# avrdmxsmt.net
KiCad netlist of a schematic drawn in EAGLE
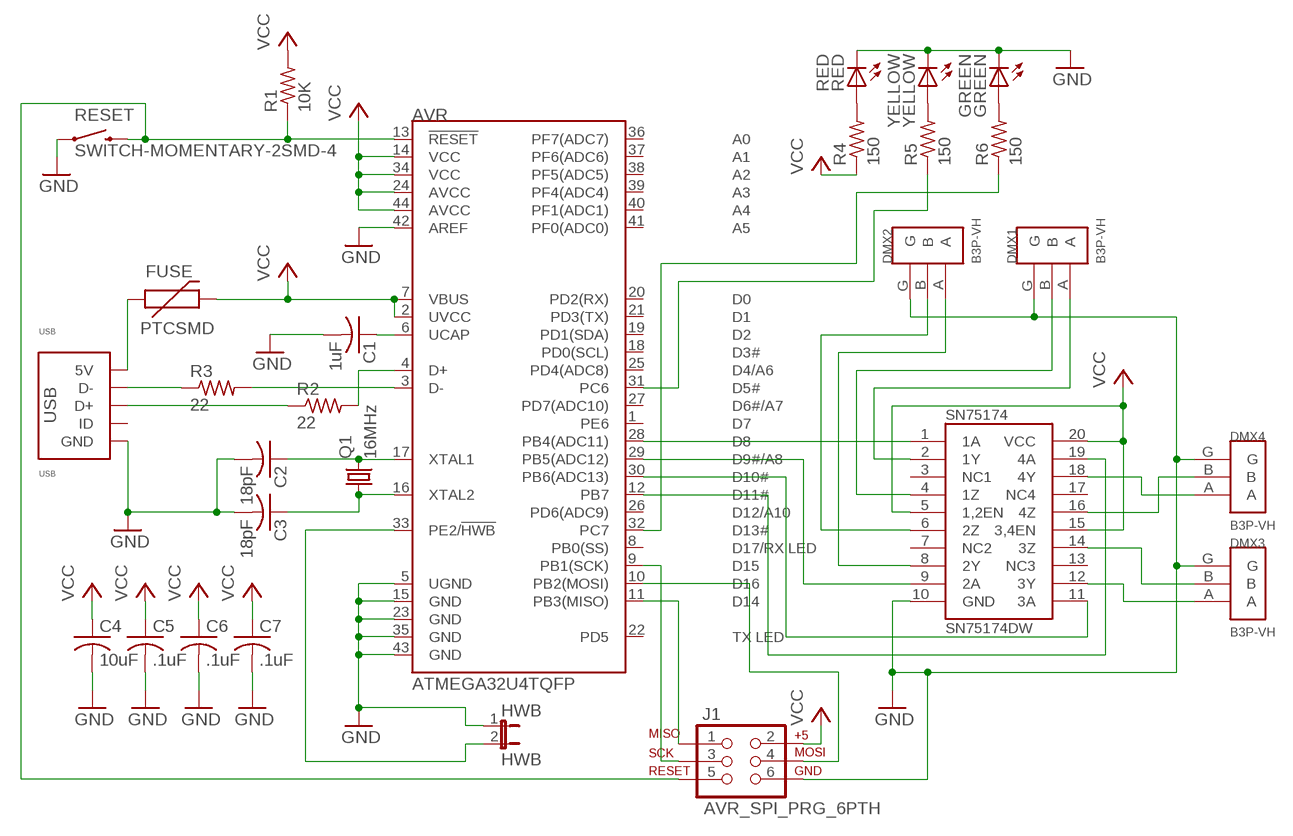
[diagram p0: schematic, sheet 1]

(export (version "E")
  (design (tool "Eeschema 10.0.6"))
  (components
    (comp (ref "AVR")
      (value "ATMEGA32U4TQFP")
      (footprint "eagle-import:SPARKFUN-DIGITALIC_TQFP44")
      (libsource (lib "eagle-import") (part "ATMEGA32U4TQFP"))
    )
    (comp (ref "C1")
      (value "1uF")
      (footprint "eagle-import:C0603K")
      (libsource (lib "eagle-import") (part "C-USC0603K"))
    )
    (comp (ref "C2")
      (value "18pF")
      (footprint "eagle-import:C0603K")
      (libsource (lib "eagle-import") (part "C-USC0603K"))
    )
    (comp (ref "C3")
      (value "18pF")
      (footprint "eagle-import:C0603K")
      (libsource (lib "eagle-import") (part "C-USC0603K"))
    )
    (comp (ref "C4")
      (value "10uF")
      (footprint "eagle-import:C0603K")
      (libsource (lib "eagle-import") (part "C-USC0603K"))
    )
    (comp (ref "C5")
      (value ".1uF")
      (footprint "eagle-import:C0603K")
      (libsource (lib "eagle-import") (part "C-USC0603K"))
    )
    (comp (ref "C6")
      (value ".1uF")
      (footprint "eagle-import:C0603K")
      (libsource (lib "eagle-import") (part "C-USC0603K"))
    )
    (comp (ref "C7")
      (value ".1uF")
      (footprint "eagle-import:C0603K")
      (libsource (lib "eagle-import") (part "C-USC0603K"))
    )
    (comp (ref "DMX1")
      (value "B3P-VH")
      (footprint "eagle-import:B3P-VH")
      (libsource (lib "eagle-import") (part "B3P-VH"))
    )
    (comp (ref "DMX2")
      (value "B3P-VH")
      (footprint "eagle-import:B3P-VH")
      (libsource (lib "eagle-import") (part "B3P-VH"))
    )
    (comp (ref "DMX3")
      (value "B3P-VH")
      (footprint "eagle-import:B3P-VH")
      (libsource (lib "eagle-import") (part "B3P-VH"))
    )
    (comp (ref "DMX4")
      (value "B3P-VH")
      (footprint "eagle-import:B3P-VH")
      (libsource (lib "eagle-import") (part "B3P-VH"))
    )
    (comp (ref "FUSE")
      (value "PTCSMD")
      (footprint "eagle-import:PTC-1206")
      (libsource (lib "eagle-import") (part "PTCSMD"))
    )
    (comp (ref "GREEN")
      (value "GREEN")
      (footprint "eagle-import:LED-0603")
      (libsource (lib "eagle-import") (part "LED-GREEN0603"))
    )
    (comp (ref "HWB")
      (value "HWB")
      (footprint "eagle-import:1X02")
      (libsource (lib "eagle-import") (part "JUMPER-2PTH"))
    )
    (comp (ref "J1")
      (value "AVR_SPI_PRG_6PTH")
      (footprint "eagle-import:2X3")
      (libsource (lib "eagle-import") (part "AVR_SPI_PRG_6PTH"))
    )
    (comp (ref "Q1")
      (value "16MHz")
      (footprint "eagle-import:SM49")
      (libsource (lib "eagle-import") (part "CRYSTALSM49"))
    )
    (comp (ref "R1")
      (value "10K")
      (footprint "eagle-import:R0603")
      (libsource (lib "eagle-import") (part "R-US_R0603"))
    )
    (comp (ref "R2")
      (value "22")
      (footprint "eagle-import:R0603")
      (libsource (lib "eagle-import") (part "R-US_R0603"))
    )
    (comp (ref "R3")
      (value "22")
      (footprint "eagle-import:R0603")
      (libsource (lib "eagle-import") (part "R-US_R0603"))
    )
    (comp (ref "R4")
      (value "150")
      (footprint "eagle-import:R0603")
      (libsource (lib "eagle-import") (part "R-US_R0603"))
    )
    (comp (ref "R5")
      (value "150")
      (footprint "eagle-import:R0603")
      (libsource (lib "eagle-import") (part "R-US_R0603"))
    )
    (comp (ref "R6")
      (value "150")
      (footprint "eagle-import:R0603")
      (libsource (lib "eagle-import") (part "R-US_R0603"))
    )
    (comp (ref "RED")
      (value "RED")
      (footprint "eagle-import:LED-0603")
      (libsource (lib "eagle-import") (part "LED-RED0603"))
    )
    (comp (ref "RESET")
      (value "SWITCH-MOMENTARY-2SMD-4")
      (footprint "eagle-import:TACTILE_SWITCH_TALL")
      (libsource (lib "eagle-import") (part "SWITCH-MOMENTARY-2SMD-4"))
    )
    (comp (ref "SN75174")
      (value "SN75174DW")
      (footprint "eagle-import:SOIC20R")
      (libsource (lib "eagle-import") (part "SN75174DW"))
    )
    (comp (ref "USB")
      (value "USB")
      (footprint "eagle-import:10118193-0001LF")
      (libsource (lib "eagle-import") (part "USB10118193-0001LF"))
    )
    (comp (ref "YELLOW")
      (value "YELLOW")
      (footprint "eagle-import:LED-0603")
      (libsource (lib "eagle-import") (part "LED-YELLOW0603"))
    )
  )
  (nets
    (net (code "1") (name "GND") (class "Default")
      (node (ref "AVR") (pin "15") (pinfunction "GND_15") (pintype "bidirectional"))
      (node (ref "AVR") (pin "23") (pinfunction "GND_23") (pintype "bidirectional"))
      (node (ref "AVR") (pin "35") (pinfunction "GND_35") (pintype "bidirectional"))
      (node (ref "AVR") (pin "42") (pinfunction "AREF_42") (pintype "bidirectional"))
      (node (ref "AVR") (pin "43") (pinfunction "GND_43") (pintype "bidirectional"))
      (node (ref "AVR") (pin "5") (pinfunction "UGND_5") (pintype "bidirectional"))
      (node (ref "C1") (pin "2") (pinfunction "2_2") (pintype "passive"))
      (node (ref "C2") (pin "2") (pinfunction "2_2") (pintype "passive"))
      (node (ref "C3") (pin "2") (pinfunction "2_2") (pintype "passive"))
      (node (ref "C4") (pin "2") (pinfunction "2_2") (pintype "passive"))
      (node (ref "C5") (pin "2") (pinfunction "2_2") (pintype "passive"))
      (node (ref "C6") (pin "2") (pinfunction "2_2") (pintype "passive"))
      (node (ref "C7") (pin "2") (pinfunction "2_2") (pintype "passive"))
      (node (ref "DMX1") (pin "G") (pinfunction "G_G") (pintype "bidirectional"))
      (node (ref "DMX2") (pin "G") (pinfunction "G_G") (pintype "bidirectional"))
      (node (ref "DMX3") (pin "G") (pinfunction "G_G") (pintype "bidirectional"))
      (node (ref "DMX4") (pin "G") (pinfunction "G_G") (pintype "bidirectional"))
      (node (ref "GREEN") (pin "C") (pinfunction "C_C") (pintype "passive"))
      (node (ref "HWB") (pin "1") (pinfunction "1_1") (pintype "passive"))
      (node (ref "J1") (pin "6") (pinfunction "6_6") (pintype "passive"))
      (node (ref "RED") (pin "C") (pinfunction "C_C") (pintype "passive"))
      (node (ref "RESET") (pin "A2") (pinfunction "1_A2") (pintype "passive"))
      (node (ref "SN75174") (pin "10") (pinfunction "GND_10") (pintype "bidirectional"))
      (node (ref "USB") (pin "5") (pinfunction "GND_5") (pintype "bidirectional"))
      (node (ref "USB") (pin "S1") (pinfunction "GND_S1") (pintype "bidirectional"))
      (node (ref "USB") (pin "S2") (pinfunction "GND_S2") (pintype "bidirectional"))
      (node (ref "USB") (pin "S3") (pinfunction "GND_S3") (pintype "bidirectional"))
      (node (ref "USB") (pin "S4") (pinfunction "GND_S4") (pintype "bidirectional"))
      (node (ref "YELLOW") (pin "C") (pinfunction "C_C") (pintype "passive"))
    )
    (net (code "2") (name "Net-(AVR-D+)") (class "Default")
      (node (ref "AVR") (pin "4") (pinfunction "D+_4") (pintype "bidirectional"))
      (node (ref "R2") (pin "2") (pinfunction "2_2") (pintype "passive"))
    )
    (net (code "3") (name "Net-(AVR-D-)") (class "Default")
      (node (ref "AVR") (pin "3") (pinfunction "D-_3") (pintype "bidirectional"))
      (node (ref "R3") (pin "2") (pinfunction "2_2") (pintype "passive"))
    )
    (net (code "4") (name "Net-(AVR-PB1(SCK))") (class "Default")
      (node (ref "AVR") (pin "9") (pinfunction "PB1(SCK)_9") (pintype "bidirectional"))
      (node (ref "J1") (pin "3") (pinfunction "3_3") (pintype "passive"))
    )
    (net (code "5") (name "Net-(AVR-PB2(MOSI))") (class "Default")
      (node (ref "AVR") (pin "10") (pinfunction "PB2(MOSI)_10") (pintype "bidirectional"))
      (node (ref "J1") (pin "4") (pinfunction "4_4") (pintype "passive"))
    )
    (net (code "6") (name "Net-(AVR-PB3(MISO))") (class "Default")
      (node (ref "AVR") (pin "11") (pinfunction "PB3(MISO)_11") (pintype "bidirectional"))
      (node (ref "J1") (pin "1") (pinfunction "1_1") (pintype "passive"))
    )
    (net (code "7") (name "Net-(AVR-PB4(ADC11))") (class "Default")
      (node (ref "AVR") (pin "28") (pinfunction "PB4(ADC11)_28") (pintype "bidirectional"))
      (node (ref "SN75174") (pin "1") (pinfunction "1A_1") (pintype "bidirectional"))
    )
    (net (code "8") (name "Net-(AVR-PB5(ADC12))") (class "Default")
      (node (ref "AVR") (pin "29") (pinfunction "PB5(ADC12)_29") (pintype "bidirectional"))
      (node (ref "SN75174") (pin "9") (pinfunction "2A_9") (pintype "bidirectional"))
    )
    (net (code "9") (name "Net-(AVR-PB6(ADC13))") (class "Default")
      (node (ref "AVR") (pin "30") (pinfunction "PB6(ADC13)_30") (pintype "bidirectional"))
      (node (ref "SN75174") (pin "11") (pinfunction "3A_11") (pintype "bidirectional"))
    )
    (net (code "10") (name "Net-(AVR-PB7)") (class "Default")
      (node (ref "AVR") (pin "12") (pinfunction "PB7_12") (pintype "bidirectional"))
      (node (ref "SN75174") (pin "19") (pinfunction "4A_19") (pintype "bidirectional"))
    )
    (net (code "11") (name "Net-(AVR-PC6)") (class "Default")
      (node (ref "AVR") (pin "31") (pinfunction "PC6_31") (pintype "bidirectional"))
      (node (ref "R5") (pin "1") (pinfunction "1_1") (pintype "passive"))
    )
    (net (code "12") (name "Net-(AVR-PC7)") (class "Default")
      (node (ref "AVR") (pin "32") (pinfunction "PC7_32") (pintype "bidirectional"))
      (node (ref "R6") (pin "1") (pinfunction "1_1") (pintype "passive"))
    )
    (net (code "13") (name "Net-(AVR-PE2{slash}~{HWB})") (class "Default")
      (node (ref "AVR") (pin "33") (pinfunction "PE2/~{HWB}_33") (pintype "bidirectional"))
      (node (ref "HWB") (pin "2") (pinfunction "2_2") (pintype "passive"))
    )
    (net (code "14") (name "Net-(AVR-UCAP)") (class "Default")
      (node (ref "AVR") (pin "6") (pinfunction "UCAP_6") (pintype "bidirectional"))
      (node (ref "C1") (pin "1") (pinfunction "1_1") (pintype "passive"))
    )
    (net (code "15") (name "Net-(AVR-XTAL1)") (class "Default")
      (node (ref "AVR") (pin "17") (pinfunction "XTAL1_17") (pintype "bidirectional"))
      (node (ref "C2") (pin "1") (pinfunction "1_1") (pintype "passive"))
      (node (ref "Q1") (pin "2") (pinfunction "2_2") (pintype "passive"))
    )
    (net (code "16") (name "Net-(AVR-XTAL2)") (class "Default")
      (node (ref "AVR") (pin "16") (pinfunction "XTAL2_16") (pintype "bidirectional"))
      (node (ref "C3") (pin "1") (pinfunction "1_1") (pintype "passive"))
      (node (ref "Q1") (pin "1") (pinfunction "1_1") (pintype "passive"))
    )
    (net (code "17") (name "Net-(AVR-~{RESET})") (class "Default")
      (node (ref "AVR") (pin "13") (pinfunction "~{RESET}_13") (pintype "bidirectional"))
      (node (ref "J1") (pin "5") (pinfunction "5_5") (pintype "passive"))
      (node (ref "R1") (pin "1") (pinfunction "1_1") (pintype "passive"))
      (node (ref "RESET") (pin "B2") (pinfunction "2_B2") (pintype "passive"))
    )
    (net (code "18") (name "Net-(GREEN-PadA)") (class "Default")
      (node (ref "GREEN") (pin "A") (pinfunction "A_A") (pintype "passive"))
      (node (ref "R6") (pin "2") (pinfunction "2_2") (pintype "passive"))
    )
    (net (code "19") (name "Net-(R4-Pad2)") (class "Default")
      (node (ref "R4") (pin "2") (pinfunction "2_2") (pintype "passive"))
      (node (ref "RED") (pin "A") (pinfunction "A_A") (pintype "passive"))
    )
    (net (code "20") (name "Net-(R5-Pad2)") (class "Default")
      (node (ref "R5") (pin "2") (pinfunction "2_2") (pintype "passive"))
      (node (ref "YELLOW") (pin "A") (pinfunction "A_A") (pintype "passive"))
    )
    (net (code "21") (name "Net-(SN75174-1Y)") (class "Default")
      (node (ref "DMX1") (pin "A") (pinfunction "A_A") (pintype "bidirectional"))
      (node (ref "SN75174") (pin "2") (pinfunction "1Y_2") (pintype "bidirectional"))
    )
    (net (code "22") (name "Net-(SN75174-1Z)") (class "Default")
      (node (ref "DMX1") (pin "B") (pinfunction "B_B") (pintype "bidirectional"))
      (node (ref "SN75174") (pin "4") (pinfunction "1Z_4") (pintype "bidirectional"))
    )
    (net (code "23") (name "Net-(SN75174-2Y)") (class "Default")
      (node (ref "DMX2") (pin "A") (pinfunction "A_A") (pintype "bidirectional"))
      (node (ref "SN75174") (pin "8") (pinfunction "2Y_8") (pintype "bidirectional"))
    )
    (net (code "24") (name "Net-(SN75174-2Z)") (class "Default")
      (node (ref "DMX2") (pin "B") (pinfunction "B_B") (pintype "bidirectional"))
      (node (ref "SN75174") (pin "6") (pinfunction "2Z_6") (pintype "bidirectional"))
    )
    (net (code "25") (name "Net-(SN75174-3Y)") (class "Default")
      (node (ref "DMX3") (pin "A") (pinfunction "A_A") (pintype "bidirectional"))
      (node (ref "SN75174") (pin "12") (pinfunction "3Y_12") (pintype "bidirectional"))
    )
    (net (code "26") (name "Net-(SN75174-3Z)") (class "Default")
      (node (ref "DMX3") (pin "B") (pinfunction "B_B") (pintype "bidirectional"))
      (node (ref "SN75174") (pin "14") (pinfunction "3Z_14") (pintype "bidirectional"))
    )
    (net (code "27") (name "Net-(SN75174-4Y)") (class "Default")
      (node (ref "DMX4") (pin "A") (pinfunction "A_A") (pintype "bidirectional"))
      (node (ref "SN75174") (pin "18") (pinfunction "4Y_18") (pintype "bidirectional"))
    )
    (net (code "28") (name "Net-(SN75174-4Z)") (class "Default")
      (node (ref "DMX4") (pin "B") (pinfunction "B_B") (pintype "bidirectional"))
      (node (ref "SN75174") (pin "16") (pinfunction "4Z_16") (pintype "bidirectional"))
    )
    (net (code "29") (name "Net-(USB-5V)") (class "Default")
      (node (ref "FUSE") (pin "1") (pinfunction "1_1") (pintype "bidirectional"))
      (node (ref "USB") (pin "1") (pinfunction "5V_1") (pintype "bidirectional"))
    )
    (net (code "30") (name "Net-(USB-D+)") (class "Default")
      (node (ref "R2") (pin "1") (pinfunction "1_1") (pintype "passive"))
      (node (ref "USB") (pin "3") (pinfunction "D+_3") (pintype "bidirectional"))
    )
    (net (code "31") (name "Net-(USB-D-)") (class "Default")
      (node (ref "R3") (pin "1") (pinfunction "1_1") (pintype "passive"))
      (node (ref "USB") (pin "2") (pinfunction "D-_2") (pintype "bidirectional"))
    )
    (net (code "32") (name "VCC") (class "Default")
      (node (ref "AVR") (pin "14") (pinfunction "VCC_14") (pintype "bidirectional"))
      (node (ref "AVR") (pin "2") (pinfunction "UVCC_2") (pintype "bidirectional"))
      (node (ref "AVR") (pin "24") (pinfunction "AVCC_24") (pintype "bidirectional"))
      (node (ref "AVR") (pin "34") (pinfunction "VCC_34") (pintype "bidirectional"))
      (node (ref "AVR") (pin "44") (pinfunction "AVCC_44") (pintype "bidirectional"))
      (node (ref "AVR") (pin "7") (pinfunction "VBUS_7") (pintype "bidirectional"))
      (node (ref "C4") (pin "1") (pinfunction "1_1") (pintype "passive"))
      (node (ref "C5") (pin "1") (pinfunction "1_1") (pintype "passive"))
      (node (ref "C6") (pin "1") (pinfunction "1_1") (pintype "passive"))
      (node (ref "C7") (pin "1") (pinfunction "1_1") (pintype "passive"))
      (node (ref "FUSE") (pin "2") (pinfunction "2_2") (pintype "bidirectional"))
      (node (ref "J1") (pin "2") (pinfunction "2_2") (pintype "passive"))
      (node (ref "R1") (pin "2") (pinfunction "2_2") (pintype "passive"))
      (node (ref "R4") (pin "1") (pinfunction "1_1") (pintype "passive"))
      (node (ref "SN75174") (pin "15") (pinfunction "3,4EN_15") (pintype "bidirectional"))
      (node (ref "SN75174") (pin "20") (pinfunction "VCC_20") (pintype "bidirectional"))
      (node (ref "SN75174") (pin "5") (pinfunction "1,2EN_5") (pintype "bidirectional"))
    )
    (net (code "33") (name "unconnected-(AVR-PB0(SS)-Pad8)") (class "Default")
      (node (ref "AVR") (pin "8") (pinfunction "PB0(SS)_8") (pintype "bidirectional"))
    )
    (net (code "34") (name "unconnected-(AVR-PD0(SCL)-Pad18)") (class "Default")
      (node (ref "AVR") (pin "18") (pinfunction "PD0(SCL)_18") (pintype "bidirectional"))
    )
    (net (code "35") (name "unconnected-(AVR-PD1(SDA)-Pad19)") (class "Default")
      (node (ref "AVR") (pin "19") (pinfunction "PD1(SDA)_19") (pintype "bidirectional"))
    )
    (net (code "36") (name "unconnected-(AVR-PD2(RX)-Pad20)") (class "Default")
      (node (ref "AVR") (pin "20") (pinfunction "PD2(RX)_20") (pintype "bidirectional"))
    )
    (net (code "37") (name "unconnected-(AVR-PD3(TX)-Pad21)") (class "Default")
      (node (ref "AVR") (pin "21") (pinfunction "PD3(TX)_21") (pintype "bidirectional"))
    )
    (net (code "38") (name "unconnected-(AVR-PD4(ADC8)-Pad25)") (class "Default")
      (node (ref "AVR") (pin "25") (pinfunction "PD4(ADC8)_25") (pintype "bidirectional"))
    )
    (net (code "39") (name "unconnected-(AVR-PD5-Pad22)") (class "Default")
      (node (ref "AVR") (pin "22") (pinfunction "PD5_22") (pintype "bidirectional"))
    )
    (net (code "40") (name "unconnected-(AVR-PD6(ADC9)-Pad26)") (class "Default")
      (node (ref "AVR") (pin "26") (pinfunction "PD6(ADC9)_26") (pintype "bidirectional"))
    )
    (net (code "41") (name "unconnected-(AVR-PD7(ADC10)-Pad27)") (class "Default")
      (node (ref "AVR") (pin "27") (pinfunction "PD7(ADC10)_27") (pintype "bidirectional"))
    )
    (net (code "42") (name "unconnected-(AVR-PE6-Pad1)") (class "Default")
      (node (ref "AVR") (pin "1") (pinfunction "PE6_1") (pintype "bidirectional"))
    )
    (net (code "43") (name "unconnected-(AVR-PF0(ADC0)-Pad41)") (class "Default")
      (node (ref "AVR") (pin "41") (pinfunction "PF0(ADC0)_41") (pintype "bidirectional"))
    )
    (net (code "44") (name "unconnected-(AVR-PF1(ADC1)-Pad40)") (class "Default")
      (node (ref "AVR") (pin "40") (pinfunction "PF1(ADC1)_40") (pintype "bidirectional"))
    )
    (net (code "45") (name "unconnected-(AVR-PF4(ADC4)-Pad39)") (class "Default")
      (node (ref "AVR") (pin "39") (pinfunction "PF4(ADC4)_39") (pintype "bidirectional"))
    )
    (net (code "46") (name "unconnected-(AVR-PF5(ADC5)-Pad38)") (class "Default")
      (node (ref "AVR") (pin "38") (pinfunction "PF5(ADC5)_38") (pintype "bidirectional"))
    )
    (net (code "47") (name "unconnected-(AVR-PF6(ADC6)-Pad37)") (class "Default")
      (node (ref "AVR") (pin "37") (pinfunction "PF6(ADC6)_37") (pintype "bidirectional"))
    )
    (net (code "48") (name "unconnected-(AVR-PF7(ADC7)-Pad36)") (class "Default")
      (node (ref "AVR") (pin "36") (pinfunction "PF7(ADC7)_36") (pintype "bidirectional"))
    )
    (net (code "49") (name "unconnected-(SN75174-NC1-Pad3)") (class "Default")
      (node (ref "SN75174") (pin "3") (pinfunction "NC1_3") (pintype "bidirectional"))
    )
    (net (code "50") (name "unconnected-(SN75174-NC2-Pad7)") (class "Default")
      (node (ref "SN75174") (pin "7") (pinfunction "NC2_7") (pintype "bidirectional"))
    )
    (net (code "51") (name "unconnected-(SN75174-NC3-Pad13)") (class "Default")
      (node (ref "SN75174") (pin "13") (pinfunction "NC3_13") (pintype "bidirectional"))
    )
    (net (code "52") (name "unconnected-(SN75174-NC4-Pad17)") (class "Default")
      (node (ref "SN75174") (pin "17") (pinfunction "NC4_17") (pintype "bidirectional"))
    )
    (net (code "53") (name "unconnected-(USB-ID-Pad4)") (class "Default")
      (node (ref "USB") (pin "4") (pinfunction "ID_4") (pintype "bidirectional"))
    )
  )
)
